# MPU6050_Schematic.net
KiCad netlist of a schematic drawn in Altium Designer
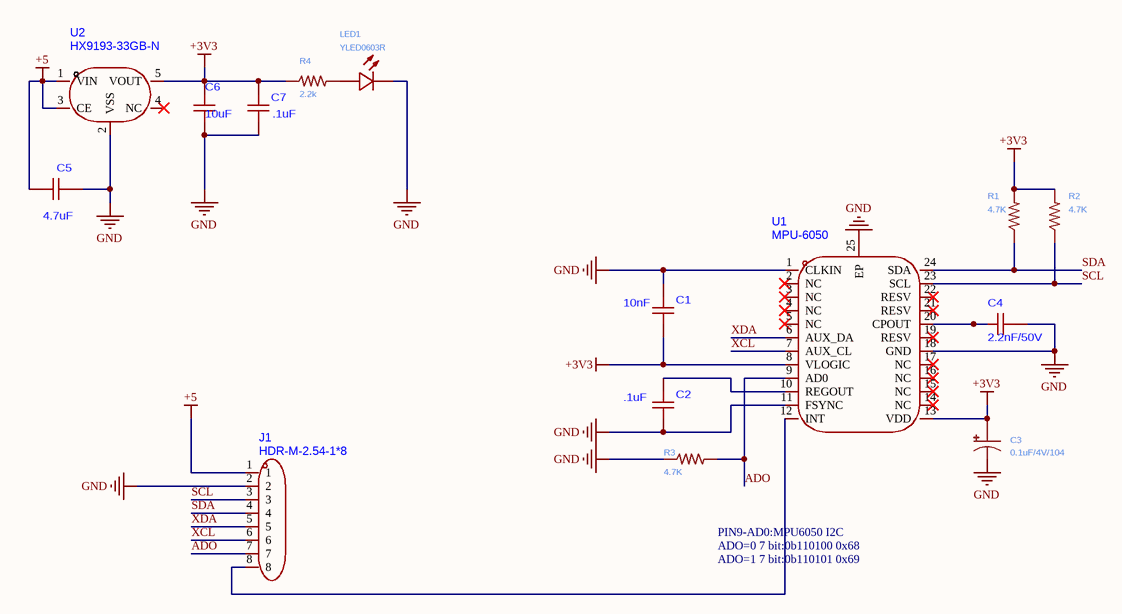
[diagram p0: MPU6050 Schematic.SchDoc]

(export (version "E")
  (design (tool "Eeschema 10.0.6"))
  (components
    (comp (ref "C1")
      (value "10nF")
      (footprint "C0402")
      (libsource (lib "altium-import") (part "root_1_1UF-C0402_"))
    )
    (comp (ref "C2")
      (value ".1uF")
      (footprint "C0402")
      (libsource (lib "altium-import") (part "root_1_1UF-C0402_"))
    )
    (comp (ref "C3")
      (value "0.1uF/4V/104")
      (footprint "CAP-SMD_L3.2-W1.6-RD")
      (libsource (lib "altium-import") (part "root_1_293D155X0010A2TE3_"))
    )
    (comp (ref "C4")
      (value "2.2nF/50V")
      (footprint "C0402")
      (libsource (lib "altium-import") (part "root_0_1UF-C0402_"))
    )
    (comp (ref "C5")
      (value "4.7uF")
      (footprint "C0402")
      (libsource (lib "altium-import") (part "root_0_1UF-C0402_"))
    )
    (comp (ref "C6")
      (value "10uF")
      (footprint "C0402")
      (libsource (lib "altium-import") (part "root_3_1UF-C0402_"))
    )
    (comp (ref "C7")
      (value ".1uF")
      (footprint "C0402")
      (libsource (lib "altium-import") (part "root_3_1UF-C0402_"))
    )
    (comp (ref "J1")
      (value "HDR-M-2.54-1*8")
      (footprint "HDR-TH_8P-P2.54-V-M")
      (fields (field (name "MANUFACTURER") "ZHOURI(洲日)") (field (name "MANUFACTURER PART") "2.54-1*8"))
      (libsource (lib "altium-import") (part "root_0_2.54-1*8_"))
    )
    (comp (ref "LED1")
      (value "YLED0603R")
      (footprint "LED0603-FD")
      (fields (field (name "MANUFACTURER") "YONGYUTAI(永裕泰)"))
      (libsource (lib "altium-import") (part "root_0_YLED0603R_"))
    )
    (comp (ref "R1")
      (value "4.7K")
      (footprint "0603")
      (libsource (lib "altium-import") (part "root_1_R_USA_"))
    )
    (comp (ref "R2")
      (value "4.7K")
      (footprint "0603")
      (libsource (lib "altium-import") (part "root_1_R_USA_"))
    )
    (comp (ref "R3")
      (value "4.7K")
      (footprint "0603")
      (libsource (lib "altium-import") (part "root_0_R_USA_"))
    )
    (comp (ref "R4")
      (value "2.2k")
      (footprint "0603")
      (libsource (lib "altium-import") (part "root_0_R_USA_"))
    )
    (comp (ref "U1")
      (value "MPU-6050")
      (footprint "QFN-24_L4.0-W4.0-P0.50-BL-EP2.7")
      (fields (field (name "MANUFACTURER") "TDK InvenSense(应美盛)"))
      (libsource (lib "altium-import") (part "root_0_MPU-6050_"))
    )
    (comp (ref "U2")
      (value "HX9193-33GB-N")
      (footprint "SOT-23-5_L2.9-W1.6-P0.95-LS2.8-BL")
      (fields (field (name "MANUFACTURER") "HX(恒佳兴)"))
      (libsource (lib "altium-import") (part "root_0_HX9193-33GB-N_"))
    )
  )
  (nets
    (net (code "1") (name "+3V3") (class "Default")
      (node (ref "C1") (pin "2") (pinfunction "2_2") (pintype "passive"))
      (node (ref "C3") (pin "1") (pinfunction "1_1") (pintype "passive"))
      (node (ref "C6") (pin "2") (pinfunction "2_2") (pintype "passive"))
      (node (ref "C7") (pin "2") (pinfunction "2_2") (pintype "passive"))
      (node (ref "R1") (pin "2") (pinfunction "2_2") (pintype "passive"))
      (node (ref "R2") (pin "2") (pinfunction "2_2") (pintype "passive"))
      (node (ref "R4") (pin "1") (pinfunction "1_1") (pintype "passive"))
      (node (ref "U1") (pin "13") (pinfunction "VDD_13") (pintype "passive"))
      (node (ref "U1") (pin "8") (pinfunction "VLOGIC_8") (pintype "passive"))
      (node (ref "U2") (pin "5") (pinfunction "VOUT_5") (pintype "passive"))
    )
    (net (code "2") (name "+5") (class "Default")
      (node (ref "C5") (pin "2") (pinfunction "2_2") (pintype "passive"))
      (node (ref "J1") (pin "1") (pinfunction "1_1") (pintype "passive"))
      (node (ref "U2") (pin "1") (pinfunction "VIN_1") (pintype "passive"))
      (node (ref "U2") (pin "3") (pinfunction "CE_3") (pintype "passive"))
    )
    (net (code "3") (name "/ADO") (class "Default")
      (node (ref "J1") (pin "7") (pinfunction "7_7") (pintype "passive"))
      (node (ref "R3") (pin "2") (pinfunction "2_2") (pintype "passive"))
      (node (ref "U1") (pin "9") (pinfunction "AD0_9") (pintype "passive"))
    )
    (net (code "4") (name "/SCL") (class "Default")
      (node (ref "J1") (pin "3") (pinfunction "3_3") (pintype "passive"))
      (node (ref "R2") (pin "1") (pinfunction "1_1") (pintype "passive"))
      (node (ref "U1") (pin "23") (pinfunction "SCL_23") (pintype "passive"))
    )
    (net (code "5") (name "/SDA") (class "Default")
      (node (ref "J1") (pin "4") (pinfunction "4_4") (pintype "passive"))
      (node (ref "R1") (pin "1") (pinfunction "1_1") (pintype "passive"))
      (node (ref "U1") (pin "24") (pinfunction "SDA_24") (pintype "passive"))
    )
    (net (code "6") (name "/XCL") (class "Default")
      (node (ref "J1") (pin "6") (pinfunction "6_6") (pintype "passive"))
      (node (ref "U1") (pin "7") (pinfunction "AUX_CL_7") (pintype "passive"))
    )
    (net (code "7") (name "/XDA") (class "Default")
      (node (ref "J1") (pin "5") (pinfunction "5_5") (pintype "passive"))
      (node (ref "U1") (pin "6") (pinfunction "AUX_DA_6") (pintype "passive"))
    )
    (net (code "8") (name "GND") (class "Default")
      (node (ref "C1") (pin "1") (pinfunction "1_1") (pintype "passive"))
      (node (ref "C2") (pin "2") (pinfunction "2_2") (pintype "passive"))
      (node (ref "C4") (pin "1") (pinfunction "1_1") (pintype "passive"))
      (node (ref "C5") (pin "1") (pinfunction "1_1") (pintype "passive"))
      (node (ref "C6") (pin "1") (pinfunction "1_1") (pintype "passive"))
      (node (ref "C7") (pin "1") (pinfunction "1_1") (pintype "passive"))
      (node (ref "J1") (pin "2") (pinfunction "2_2") (pintype "passive"))
      (node (ref "LED1") (pin "2") (pinfunction "-_2") (pintype "passive"))
      (node (ref "R3") (pin "1") (pinfunction "1_1") (pintype "passive"))
      (node (ref "U1") (pin "1") (pinfunction "CLKIN_1") (pintype "passive"))
      (node (ref "U1") (pin "11") (pinfunction "FSYNC_11") (pintype "passive"))
      (node (ref "U1") (pin "18") (pinfunction "GND_18") (pintype "passive"))
      (node (ref "U1") (pin "25") (pinfunction "EP_25") (pintype "passive"))
      (node (ref "U2") (pin "2") (pinfunction "VSS_2") (pintype "passive"))
    )
    (net (code "9") (name "Net-(LED1-+)") (class "Default")
      (node (ref "LED1") (pin "1") (pinfunction "+_1") (pintype "passive"))
      (node (ref "R4") (pin "2") (pinfunction "2_2") (pintype "passive"))
    )
    (net (code "10") (name "Net-(U1-CPOUT)") (class "Default")
      (node (ref "C4") (pin "2") (pinfunction "2_2") (pintype "passive"))
      (node (ref "U1") (pin "20") (pinfunction "CPOUT_20") (pintype "passive"))
    )
    (net (code "11") (name "Net-(U1-INT)") (class "Default")
      (node (ref "J1") (pin "8") (pinfunction "8_8") (pintype "passive"))
      (node (ref "U1") (pin "12") (pinfunction "INT_12") (pintype "passive"))
    )
    (net (code "12") (name "Net-(U1-REGOUT)") (class "Default")
      (node (ref "C2") (pin "1") (pinfunction "1_1") (pintype "passive"))
      (node (ref "U1") (pin "10") (pinfunction "REGOUT_10") (pintype "passive"))
    )
    (net (code "13") (name "unconnected-(C3-Pad2)") (class "Default")
      (node (ref "C3") (pin "2") (pinfunction "2_2") (pintype "passive"))
    )
    (net (code "14") (name "unconnected-(U1-NC-Pad2)") (class "Default")
      (node (ref "U1") (pin "2") (pinfunction "NC_2") (pintype "passive+no_connect"))
    )
    (net (code "15") (name "unconnected-(U1-NC-Pad3)") (class "Default")
      (node (ref "U1") (pin "3") (pinfunction "NC_3") (pintype "passive+no_connect"))
    )
    (net (code "16") (name "unconnected-(U1-NC-Pad4)") (class "Default")
      (node (ref "U1") (pin "4") (pinfunction "NC_4") (pintype "passive+no_connect"))
    )
    (net (code "17") (name "unconnected-(U1-NC-Pad5)") (class "Default")
      (node (ref "U1") (pin "5") (pinfunction "NC_5") (pintype "passive+no_connect"))
    )
    (net (code "18") (name "unconnected-(U1-NC-Pad14)") (class "Default")
      (node (ref "U1") (pin "14") (pinfunction "NC_14") (pintype "passive+no_connect"))
    )
    (net (code "19") (name "unconnected-(U1-NC-Pad15)") (class "Default")
      (node (ref "U1") (pin "15") (pinfunction "NC_15") (pintype "passive+no_connect"))
    )
    (net (code "20") (name "unconnected-(U1-NC-Pad16)") (class "Default")
      (node (ref "U1") (pin "16") (pinfunction "NC_16") (pintype "passive+no_connect"))
    )
    (net (code "21") (name "unconnected-(U1-NC-Pad17)") (class "Default")
      (node (ref "U1") (pin "17") (pinfunction "NC_17") (pintype "passive+no_connect"))
    )
    (net (code "22") (name "unconnected-(U1-RESV-Pad19)") (class "Default")
      (node (ref "U1") (pin "19") (pinfunction "RESV_19") (pintype "passive+no_connect"))
    )
    (net (code "23") (name "unconnected-(U1-RESV-Pad21)") (class "Default")
      (node (ref "U1") (pin "21") (pinfunction "RESV_21") (pintype "passive+no_connect"))
    )
    (net (code "24") (name "unconnected-(U1-RESV-Pad22)") (class "Default")
      (node (ref "U1") (pin "22") (pinfunction "RESV_22") (pintype "passive+no_connect"))
    )
    (net (code "25") (name "unconnected-(U2-NC-Pad4)") (class "Default")
      (node (ref "U2") (pin "4") (pinfunction "NC_4") (pintype "passive+no_connect"))
    )
  )
)
